# primary_decoupling.net
KiCad netlist of a schematic drawn in Altium Designer
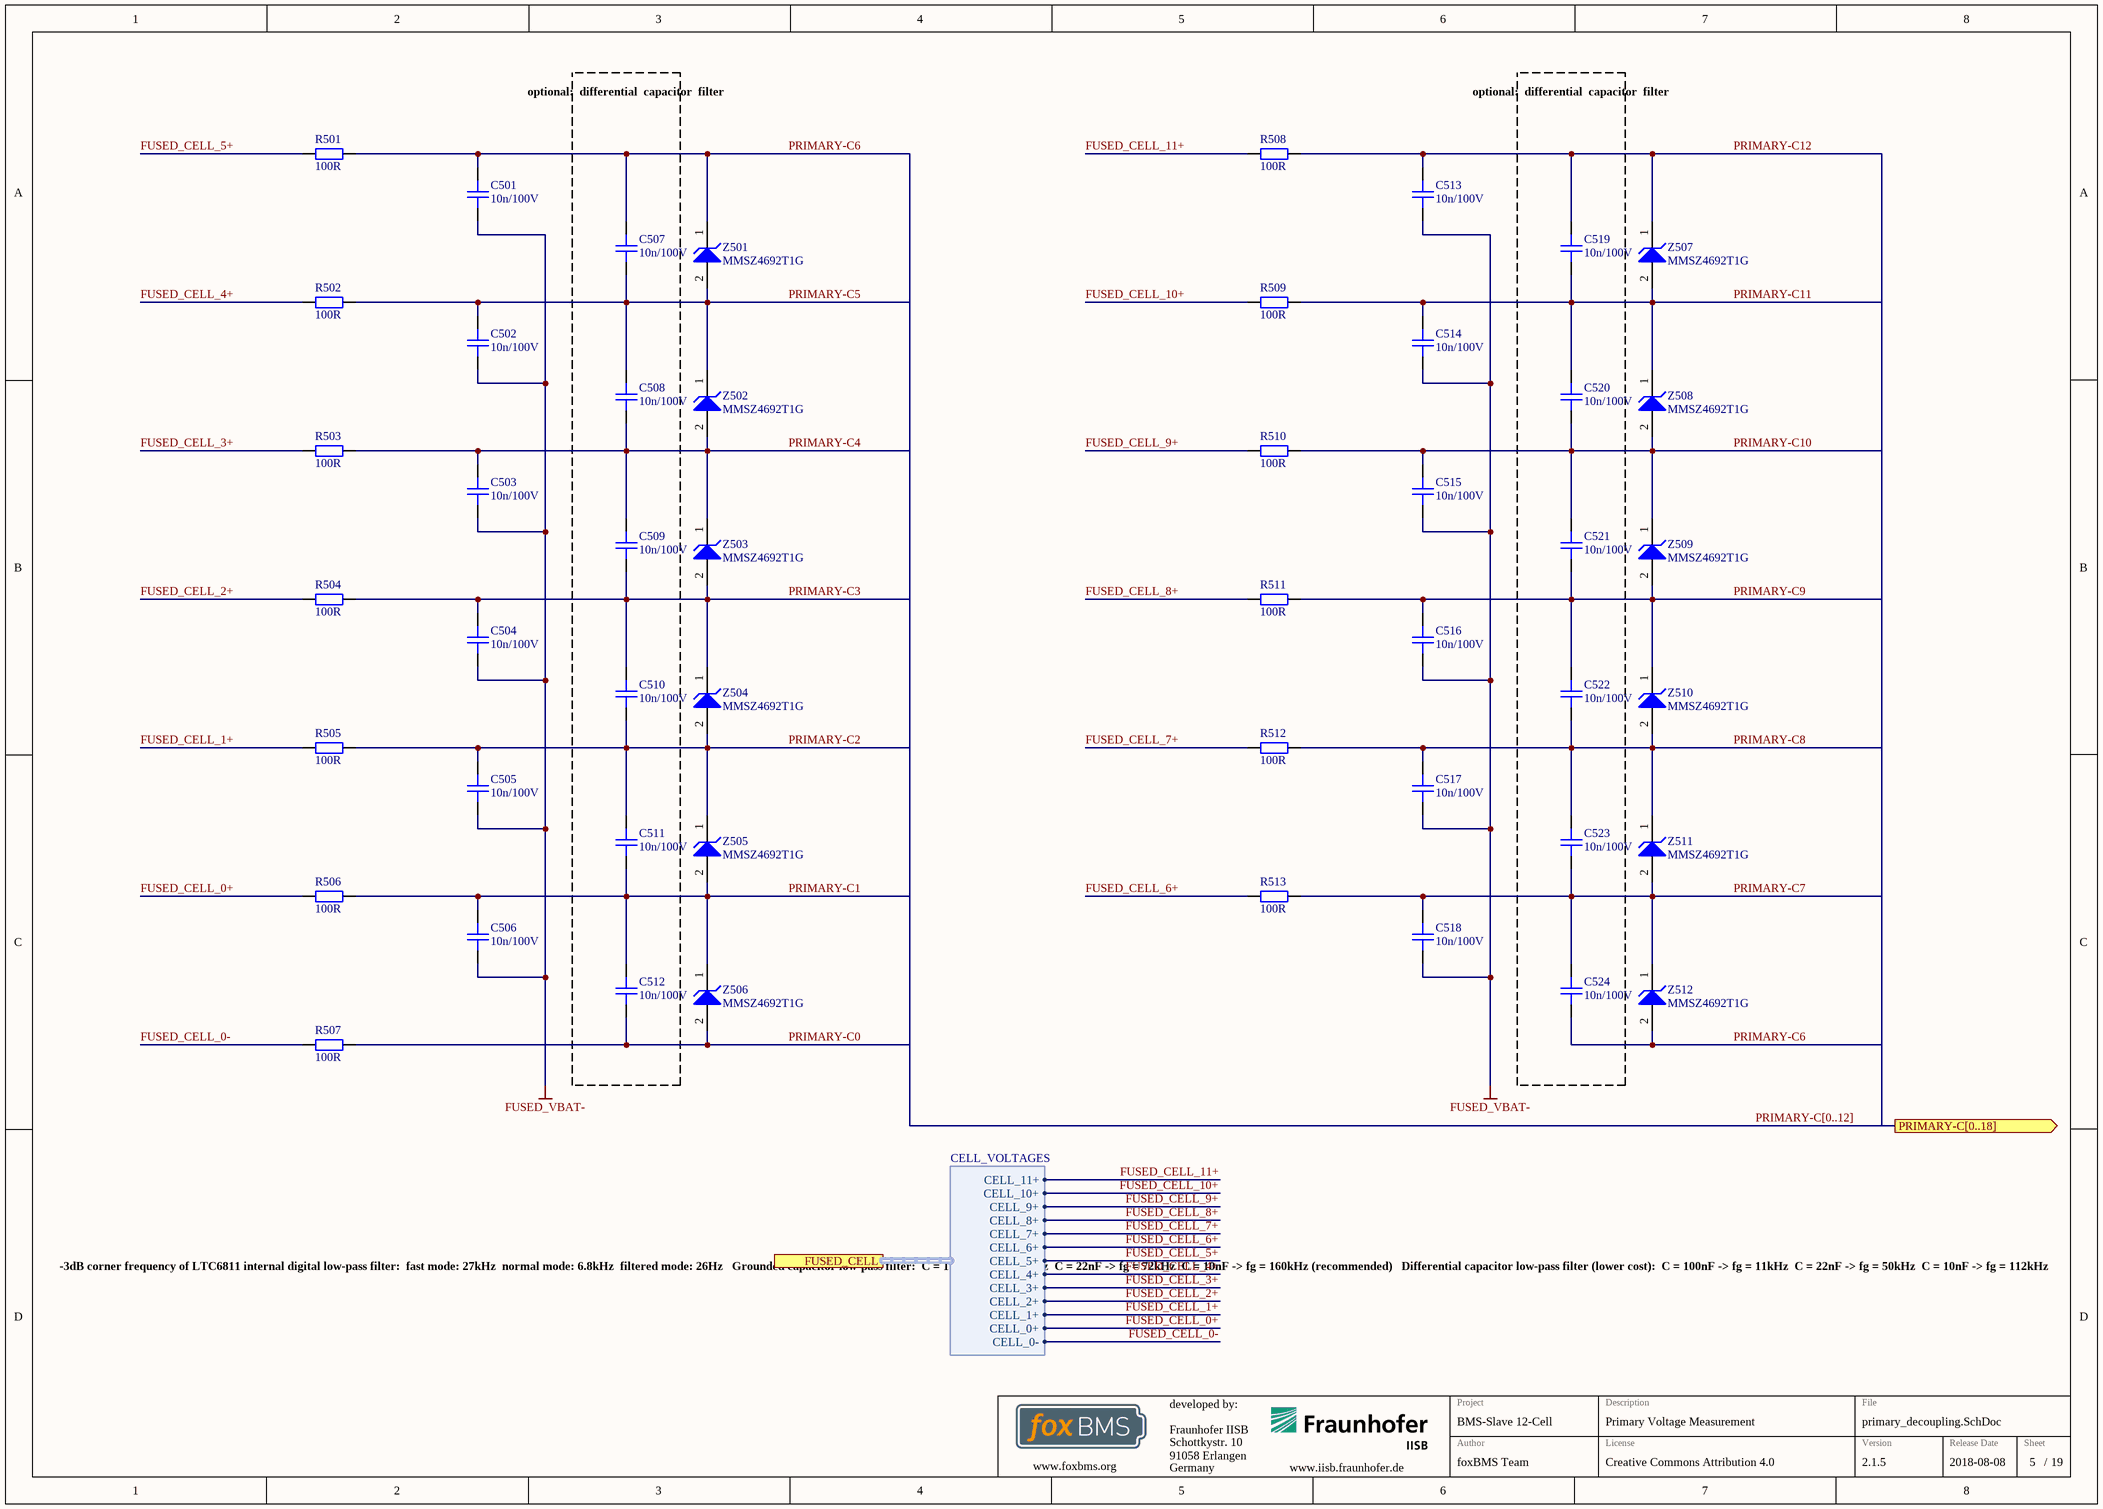
[diagram p0: primary_decoupling.SchDoc]

(export (version "E")
  (design (tool "Eeschema 10.0.6"))
  (components
    (comp (ref "C501")
      (value "10n/100V")
      (footprint "CAPC1608X08N")
      (description "MLCC")
      (fields (field (name "PART NUMBER") "gen_C_ceramic_10n_100V_X7R_0603"))
      (libsource (lib "OE750") (part "C"))
    )
    (comp (ref "C502")
      (value "10n/100V")
      (footprint "CAPC1608X08N")
      (description "MLCC")
      (fields (field (name "PART NUMBER") "gen_C_ceramic_10n_100V_X7R_0603"))
      (libsource (lib "OE750") (part "C"))
    )
    (comp (ref "C503")
      (value "10n/100V")
      (footprint "CAPC1608X08N")
      (description "MLCC")
      (fields (field (name "PART NUMBER") "gen_C_ceramic_10n_100V_X7R_0603"))
      (libsource (lib "OE750") (part "C"))
    )
    (comp (ref "C504")
      (value "10n/100V")
      (footprint "CAPC1608X08N")
      (description "MLCC")
      (fields (field (name "PART NUMBER") "gen_C_ceramic_10n_100V_X7R_0603"))
      (libsource (lib "OE750") (part "C"))
    )
    (comp (ref "C505")
      (value "10n/100V")
      (footprint "CAPC1608X08N")
      (description "MLCC")
      (fields (field (name "PART NUMBER") "gen_C_ceramic_10n_100V_X7R_0603"))
      (libsource (lib "OE750") (part "C"))
    )
    (comp (ref "C506")
      (value "10n/100V")
      (footprint "CAPC1608X08N")
      (description "MLCC")
      (fields (field (name "PART NUMBER") "gen_C_ceramic_10n_100V_X7R_0603"))
      (libsource (lib "OE750") (part "C"))
    )
    (comp (ref "C507")
      (value "10n/100V")
      (footprint "CAPC1608X08N")
      (description "MLCC")
      (fields (field (name "PART NUMBER") "gen_C_ceramic_10n_100V_X7R_0603"))
      (libsource (lib "OE750") (part "C"))
    )
    (comp (ref "C508")
      (value "10n/100V")
      (footprint "CAPC1608X08N")
      (description "MLCC")
      (fields (field (name "PART NUMBER") "gen_C_ceramic_10n_100V_X7R_0603"))
      (libsource (lib "OE750") (part "C"))
    )
    (comp (ref "C509")
      (value "10n/100V")
      (footprint "CAPC1608X08N")
      (description "MLCC")
      (fields (field (name "PART NUMBER") "gen_C_ceramic_10n_100V_X7R_0603"))
      (libsource (lib "OE750") (part "C"))
    )
    (comp (ref "C510")
      (value "10n/100V")
      (footprint "CAPC1608X08N")
      (description "MLCC")
      (fields (field (name "PART NUMBER") "gen_C_ceramic_10n_100V_X7R_0603"))
      (libsource (lib "OE750") (part "C"))
    )
    (comp (ref "C511")
      (value "10n/100V")
      (footprint "CAPC1608X08N")
      (description "MLCC")
      (fields (field (name "PART NUMBER") "gen_C_ceramic_10n_100V_X7R_0603"))
      (libsource (lib "OE750") (part "C"))
    )
    (comp (ref "C512")
      (value "10n/100V")
      (footprint "CAPC1608X08N")
      (description "MLCC")
      (fields (field (name "PART NUMBER") "gen_C_ceramic_10n_100V_X7R_0603"))
      (libsource (lib "OE750") (part "C"))
    )
    (comp (ref "C513")
      (value "10n/100V")
      (footprint "CAPC1608X08N")
      (description "MLCC")
      (fields (field (name "PART NUMBER") "gen_C_ceramic_10n_100V_X7R_0603"))
      (libsource (lib "OE750") (part "C"))
    )
    (comp (ref "C514")
      (value "10n/100V")
      (footprint "CAPC1608X08N")
      (description "MLCC")
      (fields (field (name "PART NUMBER") "gen_C_ceramic_10n_100V_X7R_0603"))
      (libsource (lib "OE750") (part "C"))
    )
    (comp (ref "C515")
      (value "10n/100V")
      (footprint "CAPC1608X08N")
      (description "MLCC")
      (fields (field (name "PART NUMBER") "gen_C_ceramic_10n_100V_X7R_0603"))
      (libsource (lib "OE750") (part "C"))
    )
    (comp (ref "C516")
      (value "10n/100V")
      (footprint "CAPC1608X08N")
      (description "MLCC")
      (fields (field (name "PART NUMBER") "gen_C_ceramic_10n_100V_X7R_0603"))
      (libsource (lib "OE750") (part "C"))
    )
    (comp (ref "C517")
      (value "10n/100V")
      (footprint "CAPC1608X08N")
      (description "MLCC")
      (fields (field (name "PART NUMBER") "gen_C_ceramic_10n_100V_X7R_0603"))
      (libsource (lib "OE750") (part "C"))
    )
    (comp (ref "C518")
      (value "10n/100V")
      (footprint "CAPC1608X08N")
      (description "MLCC")
      (fields (field (name "PART NUMBER") "gen_C_ceramic_10n_100V_X7R_0603"))
      (libsource (lib "OE750") (part "C"))
    )
    (comp (ref "C519")
      (value "10n/100V")
      (footprint "CAPC1608X08N")
      (description "MLCC")
      (fields (field (name "PART NUMBER") "gen_C_ceramic_10n_100V_X7R_0603"))
      (libsource (lib "OE750") (part "C"))
    )
    (comp (ref "C520")
      (value "10n/100V")
      (footprint "CAPC1608X08N")
      (description "MLCC")
      (fields (field (name "PART NUMBER") "gen_C_ceramic_10n_100V_X7R_0603"))
      (libsource (lib "OE750") (part "C"))
    )
    (comp (ref "C521")
      (value "10n/100V")
      (footprint "CAPC1608X08N")
      (description "MLCC")
      (fields (field (name "PART NUMBER") "gen_C_ceramic_10n_100V_X7R_0603"))
      (libsource (lib "OE750") (part "C"))
    )
    (comp (ref "C522")
      (value "10n/100V")
      (footprint "CAPC1608X08N")
      (description "MLCC")
      (fields (field (name "PART NUMBER") "gen_C_ceramic_10n_100V_X7R_0603"))
      (libsource (lib "OE750") (part "C"))
    )
    (comp (ref "C523")
      (value "10n/100V")
      (footprint "CAPC1608X08N")
      (description "MLCC")
      (fields (field (name "PART NUMBER") "gen_C_ceramic_10n_100V_X7R_0603"))
      (libsource (lib "OE750") (part "C"))
    )
    (comp (ref "C524")
      (value "10n/100V")
      (footprint "CAPC1608X08N")
      (description "MLCC")
      (fields (field (name "PART NUMBER") "gen_C_ceramic_10n_100V_X7R_0603"))
      (libsource (lib "OE750") (part "C"))
    )
    (comp (ref "R501")
      (value "100R")
      (footprint "RESC1608X05N")
      (description "SMD Resistor 100R 0603")
      (fields (field (name "PART NUMBER") "gen_R_100R_0603") (field (name "TOLERANCE") "1%"))
      (libsource (lib "OE750") (part "R"))
    )
    (comp (ref "R502")
      (value "100R")
      (footprint "RESC1608X05N")
      (description "SMD Resistor 100R 0603")
      (fields (field (name "PART NUMBER") "gen_R_100R_0603") (field (name "TOLERANCE") "1%"))
      (libsource (lib "OE750") (part "R"))
    )
    (comp (ref "R503")
      (value "100R")
      (footprint "RESC1608X05N")
      (description "SMD Resistor 100R 0603")
      (fields (field (name "PART NUMBER") "gen_R_100R_0603") (field (name "TOLERANCE") "1%"))
      (libsource (lib "OE750") (part "R"))
    )
    (comp (ref "R504")
      (value "100R")
      (footprint "RESC1608X05N")
      (description "SMD Resistor 100R 0603")
      (fields (field (name "PART NUMBER") "gen_R_100R_0603") (field (name "TOLERANCE") "1%"))
      (libsource (lib "OE750") (part "R"))
    )
    (comp (ref "R505")
      (value "100R")
      (footprint "RESC1608X05N")
      (description "SMD Resistor 100R 0603")
      (fields (field (name "PART NUMBER") "gen_R_100R_0603") (field (name "TOLERANCE") "1%"))
      (libsource (lib "OE750") (part "R"))
    )
    (comp (ref "R506")
      (value "100R")
      (footprint "RESC1608X05N")
      (description "SMD Resistor 100R 0603")
      (fields (field (name "PART NUMBER") "gen_R_100R_0603") (field (name "TOLERANCE") "1%"))
      (libsource (lib "OE750") (part "R"))
    )
    (comp (ref "R507")
      (value "100R")
      (footprint "RESC1608X05N")
      (description "SMD Resistor 100R 0603")
      (fields (field (name "PART NUMBER") "gen_R_100R_0603") (field (name "TOLERANCE") "1%"))
      (libsource (lib "OE750") (part "R"))
    )
    (comp (ref "R508")
      (value "100R")
      (footprint "RESC1608X05N")
      (description "SMD Resistor 100R 0603")
      (fields (field (name "PART NUMBER") "gen_R_100R_0603") (field (name "TOLERANCE") "1%"))
      (libsource (lib "OE750") (part "R"))
    )
    (comp (ref "R509")
      (value "100R")
      (footprint "RESC1608X05N")
      (description "SMD Resistor 100R 0603")
      (fields (field (name "PART NUMBER") "gen_R_100R_0603") (field (name "TOLERANCE") "1%"))
      (libsource (lib "OE750") (part "R"))
    )
    (comp (ref "R510")
      (value "100R")
      (footprint "RESC1608X05N")
      (description "SMD Resistor 100R 0603")
      (fields (field (name "PART NUMBER") "gen_R_100R_0603") (field (name "TOLERANCE") "1%"))
      (libsource (lib "OE750") (part "R"))
    )
    (comp (ref "R511")
      (value "100R")
      (footprint "RESC1608X05N")
      (description "SMD Resistor 100R 0603")
      (fields (field (name "PART NUMBER") "gen_R_100R_0603") (field (name "TOLERANCE") "1%"))
      (libsource (lib "OE750") (part "R"))
    )
    (comp (ref "R512")
      (value "100R")
      (footprint "RESC1608X05N")
      (description "SMD Resistor 100R 0603")
      (fields (field (name "PART NUMBER") "gen_R_100R_0603") (field (name "TOLERANCE") "1%"))
      (libsource (lib "OE750") (part "R"))
    )
    (comp (ref "R513")
      (value "100R")
      (footprint "RESC1608X05N")
      (description "SMD Resistor 100R 0603")
      (fields (field (name "PART NUMBER") "gen_R_100R_0603") (field (name "TOLERANCE") "1%"))
      (libsource (lib "OE750") (part "R"))
    )
    (comp (ref "Z501")
      (value "MMSZ4692T1G")
      (footprint "ONSC-SOD-123-2-425-04_V")
      (description "Zener Voltage Regulator, 500 mW, 2-Pin SOD-123, Pb-Free, Tape and Reel")
      (fields (field (name "MANUFACTURER") "On Semiconductor"))
      (libsource (lib "Altium Content Vault") (part "ONSC-K1A2-2"))
    )
    (comp (ref "Z502")
      (value "MMSZ4692T1G")
      (footprint "ONSC-SOD-123-2-425-04_V")
      (description "Zener Voltage Regulator, 500 mW, 2-Pin SOD-123, Pb-Free, Tape and Reel")
      (fields (field (name "MANUFACTURER") "On Semiconductor"))
      (libsource (lib "Altium Content Vault") (part "ONSC-K1A2-2"))
    )
    (comp (ref "Z503")
      (value "MMSZ4692T1G")
      (footprint "ONSC-SOD-123-2-425-04_V")
      (description "Zener Voltage Regulator, 500 mW, 2-Pin SOD-123, Pb-Free, Tape and Reel")
      (fields (field (name "MANUFACTURER") "On Semiconductor"))
      (libsource (lib "Altium Content Vault") (part "ONSC-K1A2-2"))
    )
    (comp (ref "Z504")
      (value "MMSZ4692T1G")
      (footprint "ONSC-SOD-123-2-425-04_V")
      (description "Zener Voltage Regulator, 500 mW, 2-Pin SOD-123, Pb-Free, Tape and Reel")
      (fields (field (name "MANUFACTURER") "On Semiconductor"))
      (libsource (lib "Altium Content Vault") (part "ONSC-K1A2-2"))
    )
    (comp (ref "Z505")
      (value "MMSZ4692T1G")
      (footprint "ONSC-SOD-123-2-425-04_V")
      (description "Zener Voltage Regulator, 500 mW, 2-Pin SOD-123, Pb-Free, Tape and Reel")
      (fields (field (name "MANUFACTURER") "On Semiconductor"))
      (libsource (lib "Altium Content Vault") (part "ONSC-K1A2-2"))
    )
    (comp (ref "Z506")
      (value "MMSZ4692T1G")
      (footprint "ONSC-SOD-123-2-425-04_V")
      (description "Zener Voltage Regulator, 500 mW, 2-Pin SOD-123, Pb-Free, Tape and Reel")
      (fields (field (name "MANUFACTURER") "On Semiconductor"))
      (libsource (lib "Altium Content Vault") (part "ONSC-K1A2-2"))
    )
    (comp (ref "Z507")
      (value "MMSZ4692T1G")
      (footprint "ONSC-SOD-123-2-425-04_V")
      (description "Zener Voltage Regulator, 500 mW, 2-Pin SOD-123, Pb-Free, Tape and Reel")
      (fields (field (name "MANUFACTURER") "On Semiconductor"))
      (libsource (lib "Altium Content Vault") (part "ONSC-K1A2-2"))
    )
    (comp (ref "Z508")
      (value "MMSZ4692T1G")
      (footprint "ONSC-SOD-123-2-425-04_V")
      (description "Zener Voltage Regulator, 500 mW, 2-Pin SOD-123, Pb-Free, Tape and Reel")
      (fields (field (name "MANUFACTURER") "On Semiconductor"))
      (libsource (lib "Altium Content Vault") (part "ONSC-K1A2-2"))
    )
    (comp (ref "Z509")
      (value "MMSZ4692T1G")
      (footprint "ONSC-SOD-123-2-425-04_V")
      (description "Zener Voltage Regulator, 500 mW, 2-Pin SOD-123, Pb-Free, Tape and Reel")
      (fields (field (name "MANUFACTURER") "On Semiconductor"))
      (libsource (lib "Altium Content Vault") (part "ONSC-K1A2-2"))
    )
    (comp (ref "Z510")
      (value "MMSZ4692T1G")
      (footprint "ONSC-SOD-123-2-425-04_V")
      (description "Zener Voltage Regulator, 500 mW, 2-Pin SOD-123, Pb-Free, Tape and Reel")
      (fields (field (name "MANUFACTURER") "On Semiconductor"))
      (libsource (lib "Altium Content Vault") (part "ONSC-K1A2-2"))
    )
    (comp (ref "Z511")
      (value "MMSZ4692T1G")
      (footprint "ONSC-SOD-123-2-425-04_V")
      (description "Zener Voltage Regulator, 500 mW, 2-Pin SOD-123, Pb-Free, Tape and Reel")
      (fields (field (name "MANUFACTURER") "On Semiconductor"))
      (libsource (lib "Altium Content Vault") (part "ONSC-K1A2-2"))
    )
    (comp (ref "Z512")
      (value "MMSZ4692T1G")
      (footprint "ONSC-SOD-123-2-425-04_V")
      (description "Zener Voltage Regulator, 500 mW, 2-Pin SOD-123, Pb-Free, Tape and Reel")
      (fields (field (name "MANUFACTURER") "On Semiconductor"))
      (libsource (lib "Altium Content Vault") (part "ONSC-K1A2-2"))
    )
  )
  (nets
    (net (code "2") (name "/FUSED_CELL_0+") (class "Default")
      (node (ref "R506") (pin "1") (pinfunction "1_1") (pintype "passive"))
    )
    (net (code "3") (name "/FUSED_CELL_0-") (class "Default")
      (node (ref "R507") (pin "1") (pinfunction "1_1") (pintype "passive"))
    )
    (net (code "4") (name "/FUSED_CELL_1+") (class "Default")
      (node (ref "R505") (pin "1") (pinfunction "1_1") (pintype "passive"))
    )
    (net (code "5") (name "/FUSED_CELL_2+") (class "Default")
      (node (ref "R504") (pin "1") (pinfunction "1_1") (pintype "passive"))
    )
    (net (code "6") (name "/FUSED_CELL_3+") (class "Default")
      (node (ref "R503") (pin "1") (pinfunction "1_1") (pintype "passive"))
    )
    (net (code "7") (name "/FUSED_CELL_4+") (class "Default")
      (node (ref "R502") (pin "1") (pinfunction "1_1") (pintype "passive"))
    )
    (net (code "8") (name "/FUSED_CELL_5+") (class "Default")
      (node (ref "R501") (pin "1") (pinfunction "1_1") (pintype "passive"))
    )
    (net (code "9") (name "/FUSED_CELL_6+") (class "Default")
      (node (ref "R513") (pin "1") (pinfunction "1_1") (pintype "passive"))
    )
    (net (code "10") (name "/FUSED_CELL_7+") (class "Default")
      (node (ref "R512") (pin "1") (pinfunction "1_1") (pintype "passive"))
    )
    (net (code "11") (name "/FUSED_CELL_8+") (class "Default")
      (node (ref "R511") (pin "1") (pinfunction "1_1") (pintype "passive"))
    )
    (net (code "12") (name "/FUSED_CELL_9+") (class "Default")
      (node (ref "R510") (pin "1") (pinfunction "1_1") (pintype "passive"))
    )
    (net (code "13") (name "/FUSED_CELL_10+") (class "Default")
      (node (ref "R509") (pin "1") (pinfunction "1_1") (pintype "passive"))
    )
    (net (code "14") (name "/FUSED_CELL_11+") (class "Default")
      (node (ref "R508") (pin "1") (pinfunction "1_1") (pintype "passive"))
    )
    (net (code "15") (name "/PRIMARY-C0") (class "Default")
      (node (ref "C512") (pin "2") (pinfunction "2_2") (pintype "passive"))
      (node (ref "R507") (pin "2") (pinfunction "2_2") (pintype "passive"))
      (node (ref "Z506") (pin "2") (pinfunction "A_2") (pintype "passive"))
    )
    (net (code "16") (name "/PRIMARY-C1") (class "Default")
      (node (ref "C506") (pin "1") (pinfunction "1_1") (pintype "passive"))
      (node (ref "C511") (pin "2") (pinfunction "2_2") (pintype "passive"))
      (node (ref "C512") (pin "1") (pinfunction "1_1") (pintype "passive"))
      (node (ref "R506") (pin "2") (pinfunction "2_2") (pintype "passive"))
      (node (ref "Z505") (pin "2") (pinfunction "A_2") (pintype "passive"))
      (node (ref "Z506") (pin "1") (pinfunction "K_1") (pintype "passive"))
    )
    (net (code "17") (name "/PRIMARY-C2") (class "Default")
      (node (ref "C505") (pin "1") (pinfunction "1_1") (pintype "passive"))
      (node (ref "C510") (pin "2") (pinfunction "2_2") (pintype "passive"))
      (node (ref "C511") (pin "1") (pinfunction "1_1") (pintype "passive"))
      (node (ref "R505") (pin "2") (pinfunction "2_2") (pintype "passive"))
      (node (ref "Z504") (pin "2") (pinfunction "A_2") (pintype "passive"))
      (node (ref "Z505") (pin "1") (pinfunction "K_1") (pintype "passive"))
    )
    (net (code "18") (name "/PRIMARY-C3") (class "Default")
      (node (ref "C504") (pin "1") (pinfunction "1_1") (pintype "passive"))
      (node (ref "C509") (pin "2") (pinfunction "2_2") (pintype "passive"))
      (node (ref "C510") (pin "1") (pinfunction "1_1") (pintype "passive"))
      (node (ref "R504") (pin "2") (pinfunction "2_2") (pintype "passive"))
      (node (ref "Z503") (pin "2") (pinfunction "A_2") (pintype "passive"))
      (node (ref "Z504") (pin "1") (pinfunction "K_1") (pintype "passive"))
    )
    (net (code "19") (name "/PRIMARY-C4") (class "Default")
      (node (ref "C503") (pin "1") (pinfunction "1_1") (pintype "passive"))
      (node (ref "C508") (pin "2") (pinfunction "2_2") (pintype "passive"))
      (node (ref "C509") (pin "1") (pinfunction "1_1") (pintype "passive"))
      (node (ref "R503") (pin "2") (pinfunction "2_2") (pintype "passive"))
      (node (ref "Z502") (pin "2") (pinfunction "A_2") (pintype "passive"))
      (node (ref "Z503") (pin "1") (pinfunction "K_1") (pintype "passive"))
    )
    (net (code "20") (name "/PRIMARY-C5") (class "Default")
      (node (ref "C502") (pin "1") (pinfunction "1_1") (pintype "passive"))
      (node (ref "C507") (pin "2") (pinfunction "2_2") (pintype "passive"))
      (node (ref "C508") (pin "1") (pinfunction "1_1") (pintype "passive"))
      (node (ref "R502") (pin "2") (pinfunction "2_2") (pintype "passive"))
      (node (ref "Z501") (pin "2") (pinfunction "A_2") (pintype "passive"))
      (node (ref "Z502") (pin "1") (pinfunction "K_1") (pintype "passive"))
    )
    (net (code "21") (name "/PRIMARY-C6") (class "Default")
      (node (ref "C501") (pin "1") (pinfunction "1_1") (pintype "passive"))
      (node (ref "C507") (pin "1") (pinfunction "1_1") (pintype "passive"))
      (node (ref "C524") (pin "2") (pinfunction "2_2") (pintype "passive"))
      (node (ref "R501") (pin "2") (pinfunction "2_2") (pintype "passive"))
      (node (ref "Z501") (pin "1") (pinfunction "K_1") (pintype "passive"))
      (node (ref "Z512") (pin "2") (pinfunction "A_2") (pintype "passive"))
    )
    (net (code "22") (name "/PRIMARY-C7") (class "Default")
      (node (ref "C518") (pin "1") (pinfunction "1_1") (pintype "passive"))
      (node (ref "C523") (pin "2") (pinfunction "2_2") (pintype "passive"))
      (node (ref "C524") (pin "1") (pinfunction "1_1") (pintype "passive"))
      (node (ref "R513") (pin "2") (pinfunction "2_2") (pintype "passive"))
      (node (ref "Z511") (pin "2") (pinfunction "A_2") (pintype "passive"))
      (node (ref "Z512") (pin "1") (pinfunction "K_1") (pintype "passive"))
    )
    (net (code "23") (name "/PRIMARY-C8") (class "Default")
      (node (ref "C517") (pin "1") (pinfunction "1_1") (pintype "passive"))
      (node (ref "C522") (pin "2") (pinfunction "2_2") (pintype "passive"))
      (node (ref "C523") (pin "1") (pinfunction "1_1") (pintype "passive"))
      (node (ref "R512") (pin "2") (pinfunction "2_2") (pintype "passive"))
      (node (ref "Z510") (pin "2") (pinfunction "A_2") (pintype "passive"))
      (node (ref "Z511") (pin "1") (pinfunction "K_1") (pintype "passive"))
    )
    (net (code "24") (name "/PRIMARY-C9") (class "Default")
      (node (ref "C516") (pin "1") (pinfunction "1_1") (pintype "passive"))
      (node (ref "C521") (pin "2") (pinfunction "2_2") (pintype "passive"))
      (node (ref "C522") (pin "1") (pinfunction "1_1") (pintype "passive"))
      (node (ref "R511") (pin "2") (pinfunction "2_2") (pintype "passive"))
      (node (ref "Z509") (pin "2") (pinfunction "A_2") (pintype "passive"))
      (node (ref "Z510") (pin "1") (pinfunction "K_1") (pintype "passive"))
    )
    (net (code "25") (name "/PRIMARY-C10") (class "Default")
      (node (ref "C515") (pin "1") (pinfunction "1_1") (pintype "passive"))
      (node (ref "C520") (pin "2") (pinfunction "2_2") (pintype "passive"))
      (node (ref "C521") (pin "1") (pinfunction "1_1") (pintype "passive"))
      (node (ref "R510") (pin "2") (pinfunction "2_2") (pintype "passive"))
      (node (ref "Z508") (pin "2") (pinfunction "A_2") (pintype "passive"))
      (node (ref "Z509") (pin "1") (pinfunction "K_1") (pintype "passive"))
    )
    (net (code "26") (name "/PRIMARY-C11") (class "Default")
      (node (ref "C514") (pin "1") (pinfunction "1_1") (pintype "passive"))
      (node (ref "C519") (pin "2") (pinfunction "2_2") (pintype "passive"))
      (node (ref "C520") (pin "1") (pinfunction "1_1") (pintype "passive"))
      (node (ref "R509") (pin "2") (pinfunction "2_2") (pintype "passive"))
      (node (ref "Z507") (pin "2") (pinfunction "A_2") (pintype "passive"))
      (node (ref "Z508") (pin "1") (pinfunction "K_1") (pintype "passive"))
    )
    (net (code "27") (name "/PRIMARY-C12") (class "Default")
      (node (ref "C513") (pin "1") (pinfunction "1_1") (pintype "passive"))
      (node (ref "C519") (pin "1") (pinfunction "1_1") (pintype "passive"))
      (node (ref "R508") (pin "2") (pinfunction "2_2") (pintype "passive"))
      (node (ref "Z507") (pin "1") (pinfunction "K_1") (pintype "passive"))
    )
    (net (code "30") (name "FUSED_VBAT-") (class "Default")
      (node (ref "C501") (pin "2") (pinfunction "2_2") (pintype "passive"))
      (node (ref "C502") (pin "2") (pinfunction "2_2") (pintype "passive"))
      (node (ref "C503") (pin "2") (pinfunction "2_2") (pintype "passive"))
      (node (ref "C504") (pin "2") (pinfunction "2_2") (pintype "passive"))
      (node (ref "C505") (pin "2") (pinfunction "2_2") (pintype "passive"))
      (node (ref "C506") (pin "2") (pinfunction "2_2") (pintype "passive"))
      (node (ref "C513") (pin "2") (pinfunction "2_2") (pintype "passive"))
      (node (ref "C514") (pin "2") (pinfunction "2_2") (pintype "passive"))
      (node (ref "C515") (pin "2") (pinfunction "2_2") (pintype "passive"))
      (node (ref "C516") (pin "2") (pinfunction "2_2") (pintype "passive"))
      (node (ref "C517") (pin "2") (pinfunction "2_2") (pintype "passive"))
      (node (ref "C518") (pin "2") (pinfunction "2_2") (pintype "passive"))
    )
  )
)
